# Sheet6.net
KiCad netlist of a schematic drawn in Altium Designer
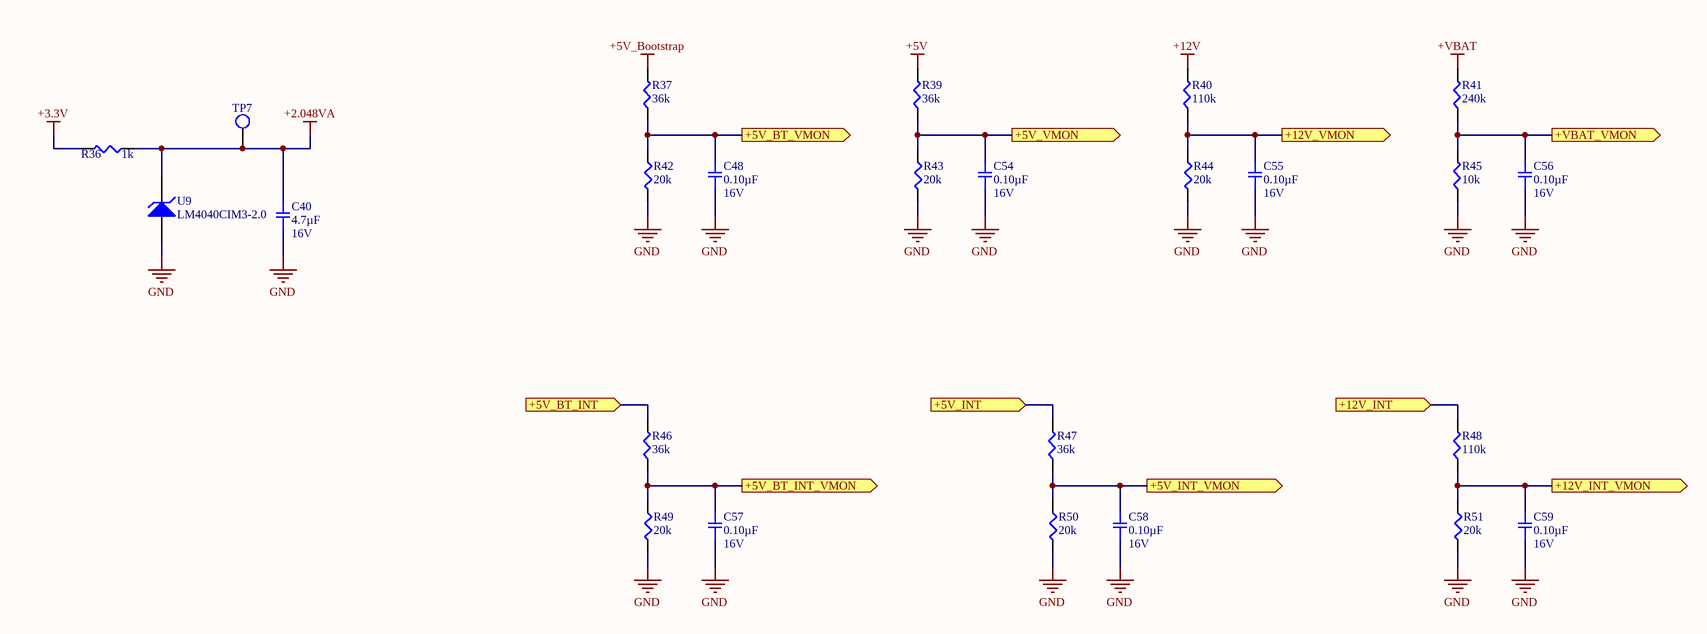
[diagram p0: Sheet6.SchDoc]

(export (version "E")
  (design (tool "Eeschema 10.0.6"))
  (components
    (comp (ref "C40")
      (value "4.7µF")
      (footprint "SMD-0805C")
      (description "CAP CER 4.7UF 16V X7R 0805")
      (fields
        (field (name "DIGI-KEY PART NUMBER") "490-10557-1-ND")
        (field (name "PART NUMBER") "GCJ21BR71C475KA01L")
        (field (name "VOLTAGE") "16V")
      )
      (libsource (lib "capacitor_murata_0805") (part "GCJ21BR71C475KA01L"))
    )
    (comp (ref "C48")
      (value "0.10µF")
      (footprint "SMD-0402C")
      (description "CAP CER 0.1UF 16V X7R 0402")
      (fields
        (field (name "DIGI-KEY PART NUMBER") "490-4759-1-ND")
        (field (name "PART NUMBER") "GCM155R71C104KA55D")
        (field (name "VOLTAGE") "16V")
      )
      (libsource (lib "capacitor_murata_0402") (part "GCM155R71C104KA55D"))
    )
    (comp (ref "C54")
      (value "0.10µF")
      (footprint "SMD-0402C")
      (description "CAP CER 0.1UF 16V X7R 0402")
      (fields
        (field (name "DIGI-KEY PART NUMBER") "490-4759-1-ND")
        (field (name "PART NUMBER") "GCM155R71C104KA55D")
        (field (name "VOLTAGE") "16V")
      )
      (libsource (lib "capacitor_murata_0402") (part "GCM155R71C104KA55D"))
    )
    (comp (ref "C55")
      (value "0.10µF")
      (footprint "SMD-0402C")
      (description "CAP CER 0.1UF 16V X7R 0402")
      (fields
        (field (name "DIGI-KEY PART NUMBER") "490-4759-1-ND")
        (field (name "PART NUMBER") "GCM155R71C104KA55D")
        (field (name "VOLTAGE") "16V")
      )
      (libsource (lib "capacitor_murata_0402") (part "GCM155R71C104KA55D"))
    )
    (comp (ref "C56")
      (value "0.10µF")
      (footprint "SMD-0402C")
      (description "CAP CER 0.1UF 16V X7R 0402")
      (fields
        (field (name "DIGI-KEY PART NUMBER") "490-4759-1-ND")
        (field (name "PART NUMBER") "GCM155R71C104KA55D")
        (field (name "VOLTAGE") "16V")
      )
      (libsource (lib "capacitor_murata_0402") (part "GCM155R71C104KA55D"))
    )
    (comp (ref "C57")
      (value "0.10µF")
      (footprint "SMD-0402C")
      (description "CAP CER 0.1UF 16V X7R 0402")
      (fields
        (field (name "DIGI-KEY PART NUMBER") "490-4759-1-ND")
        (field (name "PART NUMBER") "GCM155R71C104KA55D")
        (field (name "VOLTAGE") "16V")
      )
      (libsource (lib "capacitor_murata_0402") (part "GCM155R71C104KA55D"))
    )
    (comp (ref "C58")
      (value "0.10µF")
      (footprint "SMD-0402C")
      (description "CAP CER 0.1UF 16V X7R 0402")
      (fields
        (field (name "DIGI-KEY PART NUMBER") "490-4759-1-ND")
        (field (name "PART NUMBER") "GCM155R71C104KA55D")
        (field (name "VOLTAGE") "16V")
      )
      (libsource (lib "capacitor_murata_0402") (part "GCM155R71C104KA55D"))
    )
    (comp (ref "C59")
      (value "0.10µF")
      (footprint "SMD-0402C")
      (description "CAP CER 0.1UF 16V X7R 0402")
      (fields
        (field (name "DIGI-KEY PART NUMBER") "490-4759-1-ND")
        (field (name "PART NUMBER") "GCM155R71C104KA55D")
        (field (name "VOLTAGE") "16V")
      )
      (libsource (lib "capacitor_murata_0402") (part "GCM155R71C104KA55D"))
    )
    (comp (ref "R36")
      (value "1k")
      (footprint "SMD-0402-RES")
      (description "RES SMD 1K OHM 5% 1/10W 0402")
      (fields (field (name "PART NUMBER") "ERJ-2GEJ102X") (field (name "DIGI-KEY PART NUMBER") "P1.0KJCT-ND"))
      (libsource (lib "Panasonic_ERJ_0402") (part "ERJ-2GEJ102X"))
    )
    (comp (ref "R37")
      (value "36k")
      (footprint "SMD-0805-RES")
      (description "RES SMD 36K OHM 0.1% 1/4W 0805")
      (fields
        (field (name "PART NUMBER") "ERJ-PB6B3602V")
        (field (name "DIGI-KEY PART NUMBER") "P20770CT-ND")
      )
      (libsource (lib "Panasonic_ERJ_0805") (part "ERJ-PB6B3602V"))
    )
    (comp (ref "R39")
      (value "36k")
      (footprint "SMD-0805-RES")
      (description "RES SMD 36K OHM 0.1% 1/4W 0805")
      (fields
        (field (name "PART NUMBER") "ERJ-PB6B3602V")
        (field (name "DIGI-KEY PART NUMBER") "P20770CT-ND")
      )
      (libsource (lib "Panasonic_ERJ_0805") (part "ERJ-PB6B3602V"))
    )
    (comp (ref "R40")
      (value "110k")
      (footprint "SMD-0805-RES")
      (description "RES SMD 110K OHM 0.1% 1/4W 0805")
      (fields
        (field (name "PART NUMBER") "ERJ-PB6B1103V")
        (field (name "DIGI-KEY PART NUMBER") "P20826CT-ND")
      )
      (libsource (lib "Panasonic_ERJ_0805") (part "ERJ-PB6B1103V"))
    )
    (comp (ref "R41")
      (value "240k")
      (footprint "SMD-0805-RES")
      (description "RES SMD 240K OHM 0.1% 1/4W 0805")
      (fields
        (field (name "PART NUMBER") "ERJ-PB6B2403V")
        (field (name "DIGI-KEY PART NUMBER") "P20863CT-ND")
      )
      (libsource (lib "Panasonic_ERJ_0805") (part "ERJ-PB6B2403V"))
    )
    (comp (ref "R42")
      (value "20k")
      (footprint "SMD-0805-RES")
      (description "RES SMD 20K OHM 0.1% 1/4W 0805")
      (fields
        (field (name "PART NUMBER") "ERJ-PB6B2002V")
        (field (name "DIGI-KEY PART NUMBER") "P20740CT-ND")
      )
      (libsource (lib "Panasonic_ERJ_0805") (part "ERJ-PB6B2002V"))
    )
    (comp (ref "R43")
      (value "20k")
      (footprint "SMD-0805-RES")
      (description "RES SMD 20K OHM 0.1% 1/4W 0805")
      (fields
        (field (name "PART NUMBER") "ERJ-PB6B2002V")
        (field (name "DIGI-KEY PART NUMBER") "P20740CT-ND")
      )
      (libsource (lib "Panasonic_ERJ_0805") (part "ERJ-PB6B2002V"))
    )
    (comp (ref "R44")
      (value "20k")
      (footprint "SMD-0805-RES")
      (description "RES SMD 20K OHM 0.1% 1/4W 0805")
      (fields
        (field (name "PART NUMBER") "ERJ-PB6B2002V")
        (field (name "DIGI-KEY PART NUMBER") "P20740CT-ND")
      )
      (libsource (lib "Panasonic_ERJ_0805") (part "ERJ-PB6B2002V"))
    )
    (comp (ref "R45")
      (value "10k")
      (footprint "SMD-0805-RES")
      (description "RES SMD 10K OHM 0.1% 1/4W 0805")
      (fields
        (field (name "PART NUMBER") "ERJ-PB6B1002V")
        (field (name "DIGI-KEY PART NUMBER") "P20708CT-ND")
      )
      (libsource (lib "Panasonic_ERJ_0805") (part "ERJ-PB6B1002V"))
    )
    (comp (ref "R46")
      (value "36k")
      (footprint "SMD-0805-RES")
      (description "RES SMD 36K OHM 0.1% 1/4W 0805")
      (fields
        (field (name "PART NUMBER") "ERJ-PB6B3602V")
        (field (name "DIGI-KEY PART NUMBER") "P20770CT-ND")
      )
      (libsource (lib "Panasonic_ERJ_0805") (part "ERJ-PB6B3602V"))
    )
    (comp (ref "R47")
      (value "36k")
      (footprint "SMD-0805-RES")
      (description "RES SMD 36K OHM 0.1% 1/4W 0805")
      (fields
        (field (name "PART NUMBER") "ERJ-PB6B3602V")
        (field (name "DIGI-KEY PART NUMBER") "P20770CT-ND")
      )
      (libsource (lib "Panasonic_ERJ_0805") (part "ERJ-PB6B3602V"))
    )
    (comp (ref "R48")
      (value "110k")
      (footprint "SMD-0805-RES")
      (description "RES SMD 110K OHM 0.1% 1/4W 0805")
      (fields
        (field (name "PART NUMBER") "ERJ-PB6B1103V")
        (field (name "DIGI-KEY PART NUMBER") "P20826CT-ND")
      )
      (libsource (lib "Panasonic_ERJ_0805") (part "ERJ-PB6B1103V"))
    )
    (comp (ref "R49")
      (value "20k")
      (footprint "SMD-0805-RES")
      (description "RES SMD 20K OHM 0.1% 1/4W 0805")
      (fields
        (field (name "PART NUMBER") "ERJ-PB6B2002V")
        (field (name "DIGI-KEY PART NUMBER") "P20740CT-ND")
      )
      (libsource (lib "Panasonic_ERJ_0805") (part "ERJ-PB6B2002V"))
    )
    (comp (ref "R50")
      (value "20k")
      (footprint "SMD-0805-RES")
      (description "RES SMD 20K OHM 0.1% 1/4W 0805")
      (fields
        (field (name "PART NUMBER") "ERJ-PB6B2002V")
        (field (name "DIGI-KEY PART NUMBER") "P20740CT-ND")
      )
      (libsource (lib "Panasonic_ERJ_0805") (part "ERJ-PB6B2002V"))
    )
    (comp (ref "R51")
      (value "20k")
      (footprint "SMD-0805-RES")
      (description "RES SMD 20K OHM 0.1% 1/4W 0805")
      (fields
        (field (name "PART NUMBER") "ERJ-PB6B2002V")
        (field (name "DIGI-KEY PART NUMBER") "P20740CT-ND")
      )
      (libsource (lib "Panasonic_ERJ_0805") (part "ERJ-PB6B2002V"))
    )
    (comp (ref "TP7") (value "TP") (footprint "TP_SMD_40") (libsource (lib "TP") (part "TP")))
    (comp (ref "U9")
      (value "LM4040CIM3-2.0")
      (footprint "SOT95P237X112-3N (LM4040)")
      (libsource (lib "ModularPayload") (part "LM4040CIM3-2.0"))
    )
  )
  (nets
    (net (code "1") (name "+2.048VA") (class "Default")
      (node (ref "C40") (pin "2") (pinfunction "2_2") (pintype "passive"))
      (node (ref "R36") (pin "1") (pinfunction "1_1") (pintype "passive"))
      (node (ref "TP7") (pin "1") (pintype "passive"))
      (node (ref "U9") (pin "K") (pinfunction "K_K") (pintype "passive"))
    )
    (net (code "2") (name "+3.3V") (class "Default")
      (node (ref "R36") (pin "2") (pinfunction "2_2") (pintype "passive"))
    )
    (net (code "3") (name "+5V") (class "Default")
      (node (ref "R39") (pin "2") (pinfunction "2_2") (pintype "passive"))
    )
    (net (code "4") (name "+5V_Bootstrap") (class "Default")
      (node (ref "R37") (pin "2") (pinfunction "2_2") (pintype "passive"))
    )
    (net (code "5") (name "+12V") (class "Default")
      (node (ref "R40") (pin "2") (pinfunction "2_2") (pintype "passive"))
    )
    (net (code "6") (name "+VBAT") (class "Default")
      (node (ref "R41") (pin "2") (pinfunction "2_2") (pintype "passive"))
    )
    (net (code "7") (name "/+5V_BT_INT") (class "Default")
      (node (ref "R46") (pin "2") (pinfunction "2_2") (pintype "passive"))
    )
    (net (code "8") (name "/+5V_BT_INT_VMON") (class "Default")
      (node (ref "C57") (pin "2") (pinfunction "2_2") (pintype "passive"))
      (node (ref "R46") (pin "1") (pinfunction "1_1") (pintype "passive"))
      (node (ref "R49") (pin "1") (pinfunction "1_1") (pintype "passive"))
    )
    (net (code "9") (name "/+5V_BT_VMON") (class "Default")
      (node (ref "C48") (pin "2") (pinfunction "2_2") (pintype "passive"))
      (node (ref "R37") (pin "1") (pinfunction "1_1") (pintype "passive"))
      (node (ref "R42") (pin "1") (pinfunction "1_1") (pintype "passive"))
    )
    (net (code "10") (name "/+5V_INT") (class "Default")
      (node (ref "R47") (pin "2") (pinfunction "2_2") (pintype "passive"))
    )
    (net (code "11") (name "/+5V_INT_VMON") (class "Default")
      (node (ref "C58") (pin "2") (pinfunction "2_2") (pintype "passive"))
      (node (ref "R47") (pin "1") (pinfunction "1_1") (pintype "passive"))
      (node (ref "R50") (pin "1") (pinfunction "1_1") (pintype "passive"))
    )
    (net (code "12") (name "/+5V_VMON") (class "Default")
      (node (ref "C54") (pin "2") (pinfunction "2_2") (pintype "passive"))
      (node (ref "R39") (pin "1") (pinfunction "1_1") (pintype "passive"))
      (node (ref "R43") (pin "1") (pinfunction "1_1") (pintype "passive"))
    )
    (net (code "13") (name "/+12V_INT") (class "Default")
      (node (ref "R48") (pin "2") (pinfunction "2_2") (pintype "passive"))
    )
    (net (code "14") (name "/+12V_INT_VMON") (class "Default")
      (node (ref "C59") (pin "2") (pinfunction "2_2") (pintype "passive"))
      (node (ref "R48") (pin "1") (pinfunction "1_1") (pintype "passive"))
      (node (ref "R51") (pin "1") (pinfunction "1_1") (pintype "passive"))
    )
    (net (code "15") (name "/+12V_VMON") (class "Default")
      (node (ref "C55") (pin "2") (pinfunction "2_2") (pintype "passive"))
      (node (ref "R40") (pin "1") (pinfunction "1_1") (pintype "passive"))
      (node (ref "R44") (pin "1") (pinfunction "1_1") (pintype "passive"))
    )
    (net (code "16") (name "/+VBAT_VMON") (class "Default")
      (node (ref "C56") (pin "2") (pinfunction "2_2") (pintype "passive"))
      (node (ref "R41") (pin "1") (pinfunction "1_1") (pintype "passive"))
      (node (ref "R45") (pin "2") (pinfunction "2_2") (pintype "passive"))
    )
    (net (code "17") (name "GND") (class "Default")
      (node (ref "C40") (pin "1") (pinfunction "1_1") (pintype "passive"))
      (node (ref "C48") (pin "1") (pinfunction "1_1") (pintype "passive"))
      (node (ref "C54") (pin "1") (pinfunction "1_1") (pintype "passive"))
      (node (ref "C55") (pin "1") (pinfunction "1_1") (pintype "passive"))
      (node (ref "C56") (pin "1") (pinfunction "1_1") (pintype "passive"))
      (node (ref "C57") (pin "1") (pinfunction "1_1") (pintype "passive"))
      (node (ref "C58") (pin "1") (pinfunction "1_1") (pintype "passive"))
      (node (ref "C59") (pin "1") (pinfunction "1_1") (pintype "passive"))
      (node (ref "R42") (pin "2") (pinfunction "2_2") (pintype "passive"))
      (node (ref "R43") (pin "2") (pinfunction "2_2") (pintype "passive"))
      (node (ref "R44") (pin "2") (pinfunction "2_2") (pintype "passive"))
      (node (ref "R45") (pin "1") (pinfunction "1_1") (pintype "passive"))
      (node (ref "R49") (pin "2") (pinfunction "2_2") (pintype "passive"))
      (node (ref "R50") (pin "2") (pinfunction "2_2") (pintype "passive"))
      (node (ref "R51") (pin "2") (pinfunction "2_2") (pintype "passive"))
      (node (ref "U9") (pin "A") (pinfunction "A_A") (pintype "passive"))
    )
  )
)
